# Teclado_4x1.net
KiCad netlist of a schematic drawn in EAGLE
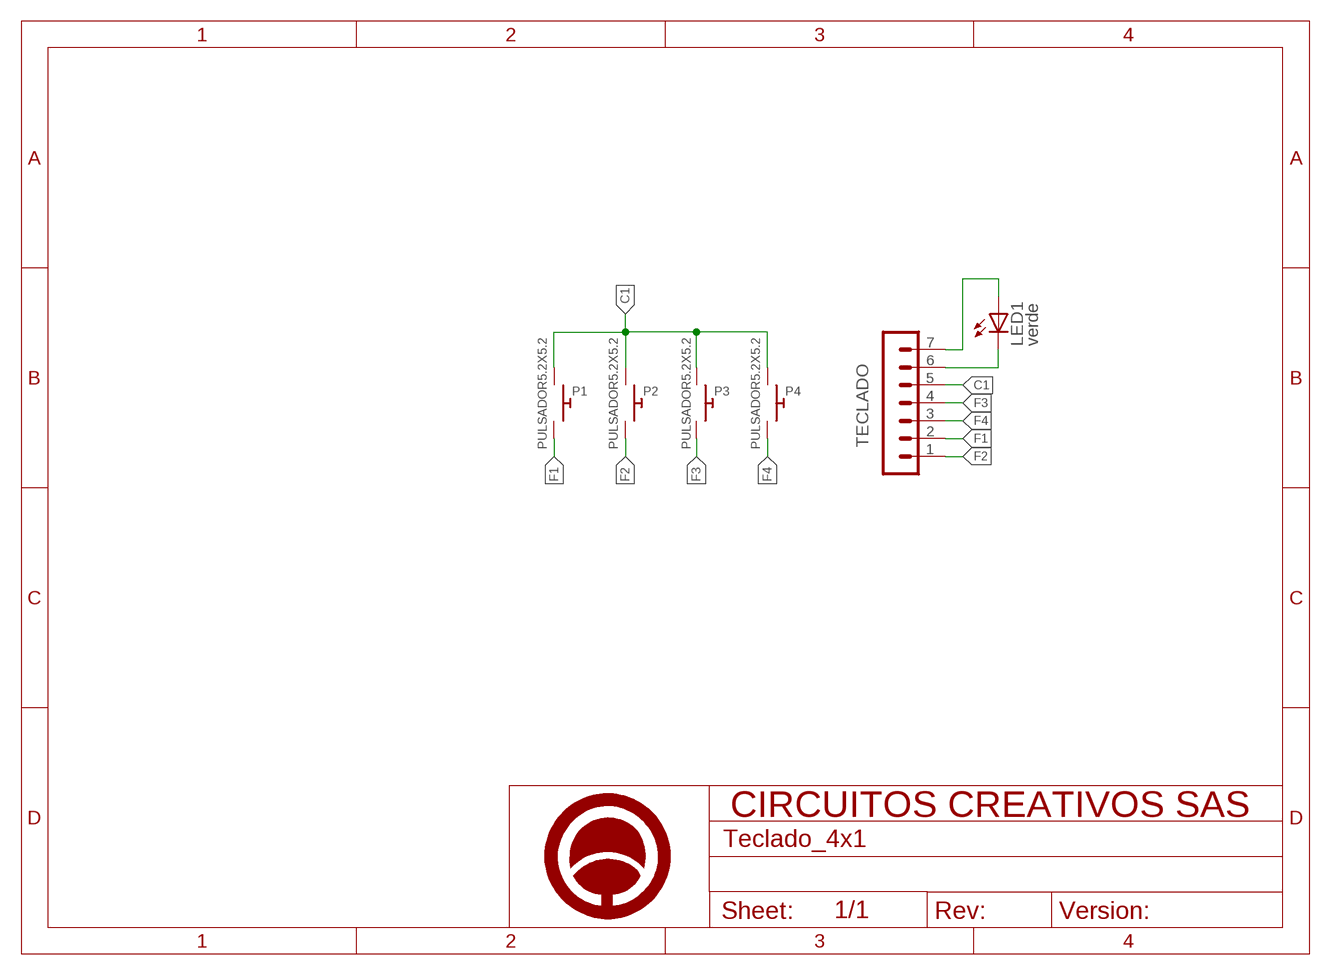
[diagram p0: schematic, sheet 1]

(export (version "E")
  (design (tool "Eeschema 10.0.6"))
  (components
    (comp (ref "LED1")
      (value "verde")
      (footprint "eagle-import:CHIP-LED0805")
      (libsource (lib "eagle-import") (part "LEDCHIP-LED0805"))
    )
    (comp (ref "P1")
      (value "PULSADOR5.2X5.2")
      (footprint "eagle-import:SMT_5.2X5.2MM")
      (libsource (lib "eagle-import") (part "PULSADOR5.2X5.2"))
    )
    (comp (ref "P2")
      (value "PULSADOR5.2X5.2")
      (footprint "eagle-import:SMT_5.2X5.2MM")
      (libsource (lib "eagle-import") (part "PULSADOR5.2X5.2"))
    )
    (comp (ref "P3")
      (value "PULSADOR5.2X5.2")
      (footprint "eagle-import:SMT_5.2X5.2MM")
      (libsource (lib "eagle-import") (part "PULSADOR5.2X5.2"))
    )
    (comp (ref "P4")
      (value "PULSADOR5.2X5.2")
      (footprint "eagle-import:SMT_5.2X5.2MM")
      (libsource (lib "eagle-import") (part "PULSADOR5.2X5.2"))
    )
    (comp (ref "TECLADO")
      (value "MA07-1")
      (footprint "eagle-import:MA07-1")
      (libsource (lib "eagle-import") (part "MA07-1"))
    )
    (comp (ref "U$1")
      (value "A5_HORIZONTAL")
      (footprint "eagle-import:LOGO")
      (libsource (lib "eagle-import") (part "A5_HORIZONTAL"))
    )
  )
  (nets
    (net (code "1") (name "C1") (class "Default")
      (node (ref "P1") (pin "1") (pinfunction "P$1_1") (pintype "passive"))
      (node (ref "P1") (pin "2") (pinfunction "P$1_2") (pintype "passive"))
      (node (ref "P2") (pin "1") (pinfunction "P$1_1") (pintype "passive"))
      (node (ref "P2") (pin "2") (pinfunction "P$1_2") (pintype "passive"))
      (node (ref "P3") (pin "1") (pinfunction "P$1_1") (pintype "passive"))
      (node (ref "P3") (pin "2") (pinfunction "P$1_2") (pintype "passive"))
      (node (ref "P4") (pin "1") (pinfunction "P$1_1") (pintype "passive"))
      (node (ref "P4") (pin "2") (pinfunction "P$1_2") (pintype "passive"))
      (node (ref "TECLADO") (pin "5") (pinfunction "5_5") (pintype "passive"))
    )
    (net (code "2") (name "F1") (class "Default")
      (node (ref "P1") (pin "3") (pinfunction "P$2_3") (pintype "passive"))
      (node (ref "P1") (pin "4") (pinfunction "P$2_4") (pintype "passive"))
      (node (ref "TECLADO") (pin "2") (pinfunction "2_2") (pintype "passive"))
    )
    (net (code "3") (name "F2") (class "Default")
      (node (ref "P2") (pin "3") (pinfunction "P$2_3") (pintype "passive"))
      (node (ref "P2") (pin "4") (pinfunction "P$2_4") (pintype "passive"))
      (node (ref "TECLADO") (pin "1") (pinfunction "1_1") (pintype "passive"))
    )
    (net (code "4") (name "F3") (class "Default")
      (node (ref "P3") (pin "3") (pinfunction "P$2_3") (pintype "passive"))
      (node (ref "P3") (pin "4") (pinfunction "P$2_4") (pintype "passive"))
      (node (ref "TECLADO") (pin "4") (pinfunction "4_4") (pintype "passive"))
    )
    (net (code "5") (name "F4") (class "Default")
      (node (ref "P4") (pin "3") (pinfunction "P$2_3") (pintype "passive"))
      (node (ref "P4") (pin "4") (pinfunction "P$2_4") (pintype "passive"))
      (node (ref "TECLADO") (pin "3") (pinfunction "3_3") (pintype "passive"))
    )
    (net (code "6") (name "Net-(LED1-PadA)") (class "Default")
      (node (ref "LED1") (pin "A") (pinfunction "A_A") (pintype "passive"))
      (node (ref "TECLADO") (pin "7") (pinfunction "7_7") (pintype "passive"))
    )
    (net (code "7") (name "Net-(LED1-PadC)") (class "Default")
      (node (ref "LED1") (pin "C") (pinfunction "C_C") (pintype "passive"))
      (node (ref "TECLADO") (pin "6") (pinfunction "6_6") (pintype "passive"))
    )
  )
)
